# oshi-fuse-board-mk-3_mini-ato.net
KiCad netlist of a schematic drawn in EAGLE
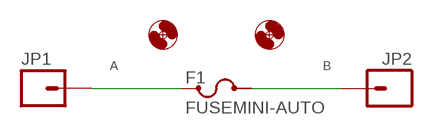
[diagram p0: schematic, sheet 1]

(export (version "E")
  (design (tool "Eeschema 10.0.6"))
  (components
    (comp (ref "F1")
      (value "FUSEMINI-AUTO")
      (footprint "eagle-import:KEYSTONE-MINI-AUTO-FUSE-HOLDER")
      (libsource (lib "eagle-import") (part "FUSEMINI-AUTO"))
    )
    (comp (ref "H1")
      (value "HOLE#4")
      (footprint "eagle-import:HOLE-#4")
      (libsource (lib "eagle-import") (part "HOLE#4"))
    )
    (comp (ref "H2")
      (value "HOLE#4")
      (footprint "eagle-import:HOLE-#4")
      (libsource (lib "eagle-import") (part "HOLE#4"))
    )
    (comp (ref "JP1")
      (value "M01SCREWITGOOD")
      (footprint "eagle-import:1X01-RING-TERM-6-32-FAT")
      (libsource (lib "eagle-import") (part "M01SCREWITGOOD"))
    )
    (comp (ref "JP2")
      (value "M01SCREWITGOOD")
      (footprint "eagle-import:1X01-RING-TERM-6-32-FAT")
      (libsource (lib "eagle-import") (part "M01SCREWITGOOD"))
    )
  )
  (nets
    (net (code "1") (name "/A") (class "Default")
      (node (ref "F1") (pin "P1@1") (pinfunction "1_P1@1") (pintype "passive"))
      (node (ref "F1") (pin "P1@2") (pinfunction "1_P1@2") (pintype "passive"))
      (node (ref "JP1") (pin "P$1") (pinfunction "1_P$1") (pintype "passive"))
      (node (ref "JP1") (pin "P$2") (pinfunction "1_P$2") (pintype "passive"))
      (node (ref "JP1") (pin "P$3") (pinfunction "1_P$3") (pintype "passive"))
      (node (ref "JP1") (pin "P$4") (pinfunction "1_P$4") (pintype "passive"))
    )
    (net (code "2") (name "/B") (class "Default")
      (node (ref "F1") (pin "P2@1") (pinfunction "2_P2@1") (pintype "passive"))
      (node (ref "F1") (pin "P2@2") (pinfunction "2_P2@2") (pintype "passive"))
      (node (ref "JP2") (pin "P$1") (pinfunction "1_P$1") (pintype "passive"))
      (node (ref "JP2") (pin "P$2") (pinfunction "1_P$2") (pintype "passive"))
      (node (ref "JP2") (pin "P$3") (pinfunction "1_P$3") (pintype "passive"))
      (node (ref "JP2") (pin "P$4") (pinfunction "1_P$4") (pintype "passive"))
    )
  )
)
